# Arduino-Teensy-v43_PLUS_ESP-12E.net
KiCad netlist of a schematic drawn in EAGLE
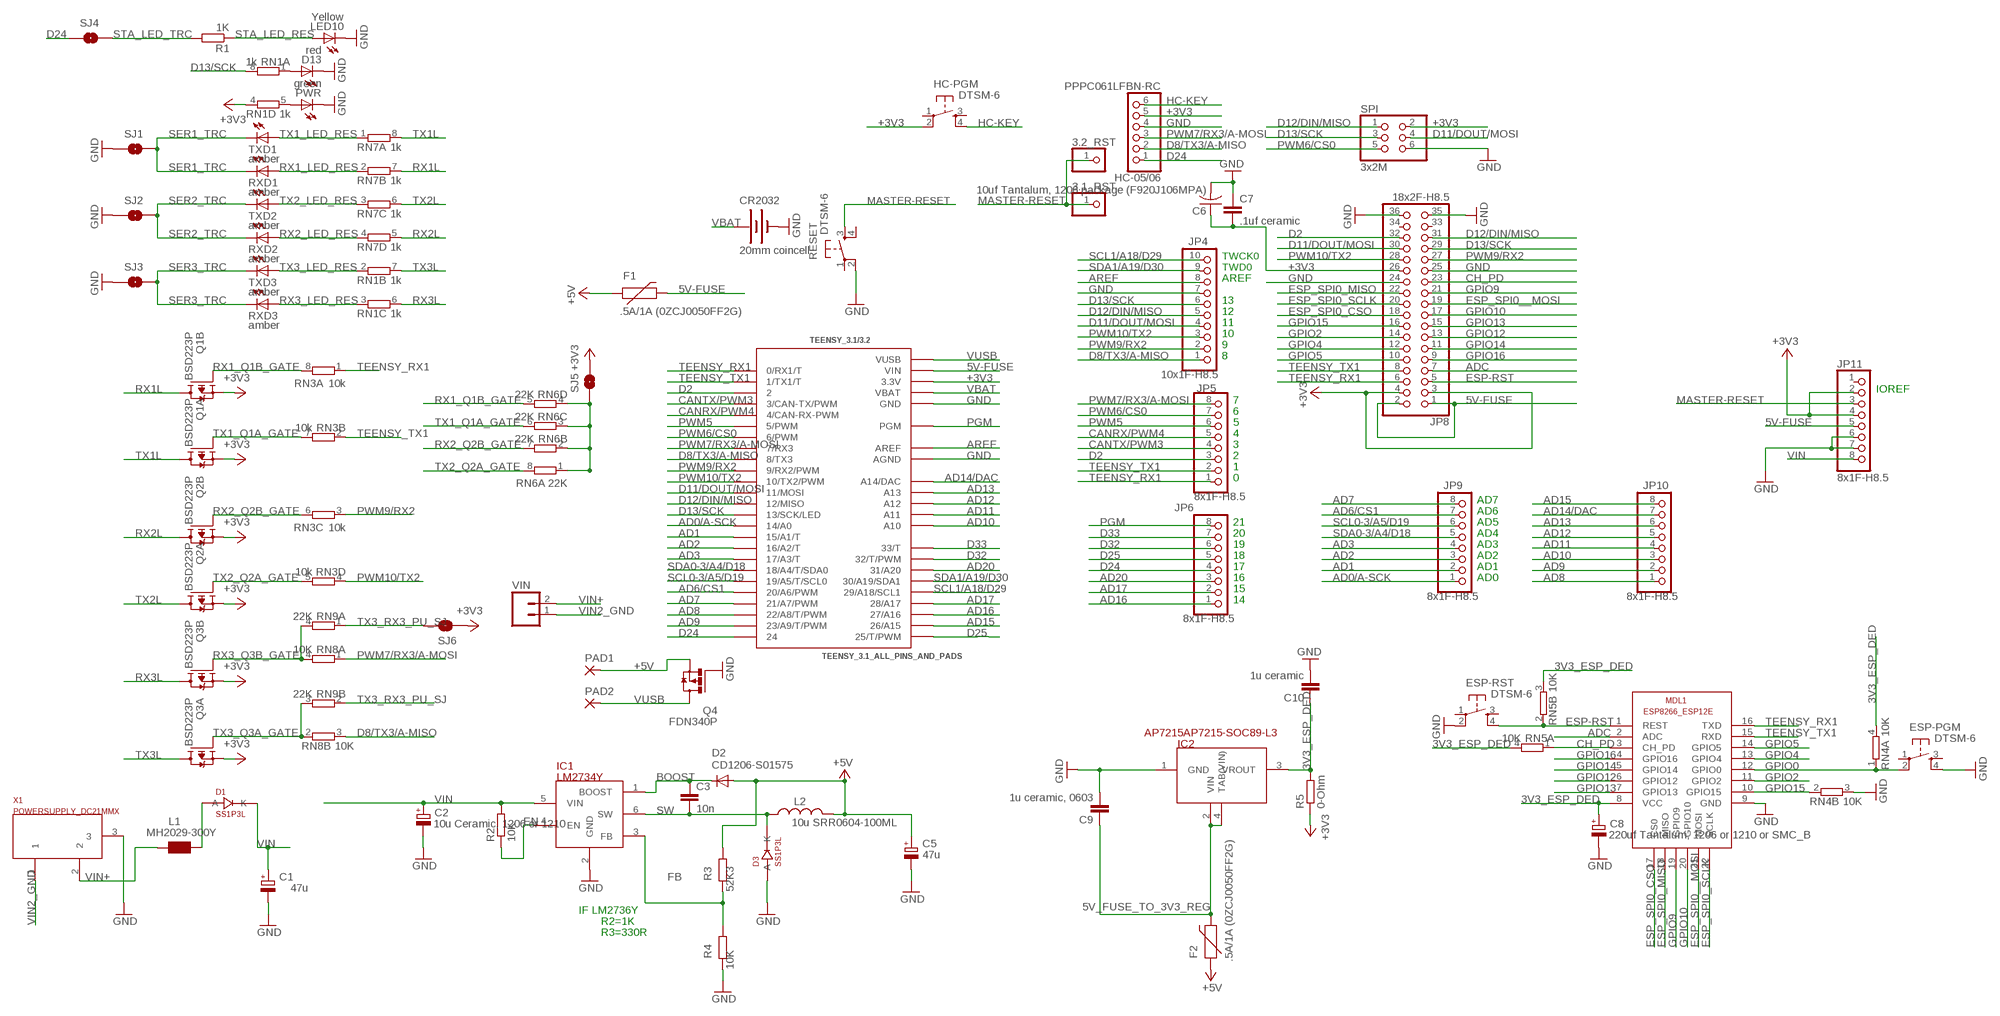
[diagram p0: schematic, sheet 1]

(export (version "E")
  (design (tool "Eeschema 10.0.6"))
  (components
    (comp (ref "3.1_RST")
      (value "PINHD-1X1CB")
      (footprint "eagle-import:1X01-CLEANBIG")
      (libsource (lib "eagle-import") (part "PINHD-1X1CB"))
    )
    (comp (ref "3.2_RST")
      (value "PINHD-1X1CB")
      (footprint "eagle-import:1X01-CLEANBIG")
      (libsource (lib "eagle-import") (part "PINHD-1X1CB"))
    )
    (comp (ref "C1")
      (value "47u")
      (footprint "eagle-import:PANASONIC_D")
      (libsource (lib "eagle-import") (part "CPOL-EUD"))
    )
    (comp (ref "C2")
      (value "10u Ceramic, 1206 or 1210")
      (footprint "eagle-import:SMC_B")
      (libsource (lib "eagle-import") (part "CPOL-EUSMCB"))
    )
    (comp (ref "C3")
      (value "10n")
      (footprint "eagle-import:C0603-ROUND")
      (libsource (lib "eagle-import") (part "C-EUC0603"))
    )
    (comp (ref "C5")
      (value "47u")
      (footprint "eagle-import:PANASONIC_D")
      (libsource (lib "eagle-import") (part "CPOL-EUD"))
    )
    (comp (ref "C6")
      (value "10uf Tantalum, 1206 package (F920J106MPA)")
      (footprint "eagle-import:C0805")
      (libsource (lib "eagle-import") (part "C-USC0805"))
    )
    (comp (ref "C7")
      (value ".1uf ceramic")
      (footprint "eagle-import:C0603-ROUND")
      (libsource (lib "eagle-import") (part "C-EUC0603"))
    )
    (comp (ref "C8")
      (value "220uf Tantalum, 1206 or 1210 or SMC_B")
      (footprint "eagle-import:SMC_B")
      (libsource (lib "eagle-import") (part "CPOL-EUSMCB"))
    )
    (comp (ref "C9")
      (value "1u ceramic, 0603")
      (footprint "eagle-import:C0603-ROUND")
      (libsource (lib "eagle-import") (part "C-EUC0603"))
    )
    (comp (ref "C10")
      (value "1u ceramic")
      (footprint "eagle-import:C0603-ROUND")
      (libsource (lib "eagle-import") (part "C-EUC0603"))
    )
    (comp (ref "CR2032")
      (value "20mm coincell")
      (footprint "eagle-import:BATTCON_20MM_4LEGS")
      (libsource (lib "eagle-import") (part "BATTERY20MM_4LEGS"))
    )
    (comp (ref "D1")
      (value "SS1P3L")
      (footprint "eagle-import:DO220AAL")
      (libsource (lib "eagle-import") (part "SS1P3L"))
    )
    (comp (ref "D2")
      (value "CD1206-S01575")
      (footprint "eagle-import:MINIMELF")
      (libsource (lib "eagle-import") (part "DIODE-MINIMELF"))
    )
    (comp (ref "D3")
      (value "SS1P3L")
      (footprint "eagle-import:DO220AAL")
      (libsource (lib "eagle-import") (part "SS1P3L"))
    )
    (comp (ref "D13")
      (value "red")
      (footprint "eagle-import:CHIPLED_0805")
      (libsource (lib "eagle-import") (part "LEDCHIPLED_0805"))
    )
    (comp (ref "ESP-PGM")
      (value "DTSM-6")
      (footprint "eagle-import:DTSM-6")
      (libsource (lib "eagle-import") (part "DTSM-6"))
    )
    (comp (ref "ESP-RST")
      (value "DTSM-6")
      (footprint "eagle-import:DTSM-6")
      (libsource (lib "eagle-import") (part "DTSM-6"))
    )
    (comp (ref "F1")
      (value ".5A/1A (0ZCJ0050FF2G)")
      (footprint "eagle-import:PTC-1206")
      (libsource (lib "eagle-import") (part "PTCSMD"))
    )
    (comp (ref "F2")
      (value ".5A/1A (0ZCJ0050FF2G)")
      (footprint "eagle-import:PTC-1206")
      (libsource (lib "eagle-import") (part "PTCSMD"))
    )
    (comp (ref "HC-05/06")
      (value "PPPC061LFBN-RC")
      (footprint "eagle-import:1X06")
      (libsource (lib "eagle-import") (part "PINHD-1X6"))
    )
    (comp (ref "HC-PGM")
      (value "DTSM-6")
      (footprint "eagle-import:DTSM-6")
      (libsource (lib "eagle-import") (part "DTSM-6"))
    )
    (comp (ref "IC1")
      (value "LM2734Y")
      (footprint "eagle-import:SOT23-6")
      (libsource (lib "eagle-import") (part "LM2736Y"))
    )
    (comp (ref "IC2")
      (value "AP7215AP7215-SOC89-L3")
      (footprint "eagle-import:SOC89-L3")
      (libsource (lib "eagle-import") (part "AP7215AP7215-SOC89-L3"))
    )
    (comp (ref "JP4")
      (value "10x1F-H8.5")
      (footprint "eagle-import:1X10")
      (libsource (lib "eagle-import") (part "PINHD-1X10"))
    )
    (comp (ref "JP5")
      (value "8x1F-H8.5")
      (footprint "eagle-import:1X08")
      (libsource (lib "eagle-import") (part "PINHD-1X8"))
    )
    (comp (ref "JP6")
      (value "8x1F-H8.5")
      (footprint "eagle-import:1X08")
      (libsource (lib "eagle-import") (part "PINHD-1X8"))
    )
    (comp (ref "JP8")
      (value "18x2F-H8.5")
      (footprint "eagle-import:2X18")
      (libsource (lib "eagle-import") (part "PINHD-2X18"))
    )
    (comp (ref "JP9")
      (value "8x1F-H8.5")
      (footprint "eagle-import:1X08")
      (libsource (lib "eagle-import") (part "PINHD-1X8"))
    )
    (comp (ref "JP10")
      (value "8x1F-H8.5")
      (footprint "eagle-import:1X08")
      (libsource (lib "eagle-import") (part "PINHD-1X8"))
    )
    (comp (ref "JP11")
      (value "8x1F-H8.5")
      (footprint "eagle-import:1X08")
      (libsource (lib "eagle-import") (part "PINHD-1X8"))
    )
    (comp (ref "L1")
      (value "MH2029-300Y")
      (footprint "eagle-import:0805")
      (libsource (lib "eagle-import") (part "WE-CBF_0805"))
    )
    (comp (ref "L2")
      (value "10u SRR0604-100ML")
      (footprint "eagle-import:SRR0604")
      (libsource (lib "eagle-import") (part "L-USSRR0604"))
    )
    (comp (ref "LED10")
      (value "Yellow")
      (footprint "eagle-import:CHIPLED_0805")
      (libsource (lib "eagle-import") (part "LEDCHIPLED_0805"))
    )
    (comp (ref "MDL1")
      (value "ESP8266-12E)")
      (footprint "eagle-import:ESP8266-ESP12E")
      (libsource (lib "eagle-import") (part "ESP8266-12EESP8266-ESP12E"))
    )
    (comp (ref "PAD1")
      (value "SMD2")
      (footprint "eagle-import:SMD1,27-2,54")
      (libsource (lib "eagle-import") (part "SMD2"))
    )
    (comp (ref "PAD2")
      (value "SMD2")
      (footprint "eagle-import:SMD1,27-2,54")
      (libsource (lib "eagle-import") (part "SMD2"))
    )
    (comp (ref "PWR")
      (value "green")
      (footprint "eagle-import:CHIPLED_0805")
      (libsource (lib "eagle-import") (part "LEDCHIPLED_0805"))
    )
    (comp (ref "Q1")
      (value "BSD223P")
      (footprint "eagle-import:SOT363_INFINEON")
      (libsource (lib "eagle-import") (part "BSD223P"))
    )
    (comp (ref "Q2")
      (value "BSD223P")
      (footprint "eagle-import:SOT363_INFINEON")
      (libsource (lib "eagle-import") (part "BSD223P"))
    )
    (comp (ref "Q3")
      (value "BSD223P")
      (footprint "eagle-import:SOT363_INFINEON")
      (libsource (lib "eagle-import") (part "BSD223P"))
    )
    (comp (ref "Q4")
      (value "FDN340P")
      (footprint "eagle-import:SUPER-SOT3")
      (libsource (lib "eagle-import") (part "FDN360P"))
    )
    (comp (ref "R1")
      (value "1K")
      (footprint "eagle-import:R0603")
      (libsource (lib "eagle-import") (part "rcl_R-EU_R0603"))
    )
    (comp (ref "R2")
      (value "10K")
      (footprint "eagle-import:R0603")
      (libsource (lib "eagle-import") (part "rcl_R-EU_R0603"))
    )
    (comp (ref "R3")
      (value "52K3")
      (footprint "eagle-import:R0603-ROUND")
      (libsource (lib "eagle-import") (part "R-EU_0603-RND"))
    )
    (comp (ref "R4")
      (value "10K")
      (footprint "eagle-import:R0603-ROUND")
      (libsource (lib "eagle-import") (part "R-EU_0603-RND"))
    )
    (comp (ref "R5")
      (value "0-Ohm")
      (footprint "eagle-import:R0603")
      (libsource (lib "eagle-import") (part "rcl_R-EU_R0603"))
    )
    (comp (ref "RESET")
      (value "DTSM-6")
      (footprint "eagle-import:DTSM-6")
      (libsource (lib "eagle-import") (part "DTSM-6"))
    )
    (comp (ref "RN1")
      (value "1k")
      (footprint "eagle-import:CAT16")
      (libsource (lib "eagle-import") (part "4R-NCAT16"))
    )
    (comp (ref "RN3")
      (value "10k")
      (footprint "eagle-import:CAT16")
      (libsource (lib "eagle-import") (part "4R-NCAT16"))
    )
    (comp (ref "RN4")
      (value "10K")
      (footprint "eagle-import:EXB34V")
      (libsource (lib "eagle-import") (part "2R-NEXB34V"))
    )
    (comp (ref "RN5")
      (value "10K")
      (footprint "eagle-import:EXB34V")
      (libsource (lib "eagle-import") (part "2R-NEXB34V"))
    )
    (comp (ref "RN6")
      (value "22K")
      (footprint "eagle-import:CAT16")
      (libsource (lib "eagle-import") (part "4R-NCAT16"))
    )
    (comp (ref "RN7")
      (value "1k")
      (footprint "eagle-import:CAT16")
      (libsource (lib "eagle-import") (part "4R-NCAT16"))
    )
    (comp (ref "RN8")
      (value "10K")
      (footprint "eagle-import:EXB34V")
      (libsource (lib "eagle-import") (part "2R-NEXB34V"))
    )
    (comp (ref "RN9")
      (value "22K")
      (footprint "eagle-import:EXB34V")
      (libsource (lib "eagle-import") (part "2R-NEXB34V"))
    )
    (comp (ref "RXD1")
      (value "amber")
      (footprint "eagle-import:CHIPLED_0805")
      (libsource (lib "eagle-import") (part "LEDCHIPLED_0805"))
    )
    (comp (ref "RXD2")
      (value "amber")
      (footprint "eagle-import:CHIPLED_0805")
      (libsource (lib "eagle-import") (part "LEDCHIPLED_0805"))
    )
    (comp (ref "RXD3")
      (value "amber")
      (footprint "eagle-import:CHIPLED_0805")
      (libsource (lib "eagle-import") (part "LEDCHIPLED_0805"))
    )
    (comp (ref "SJ1")
      (value "SOLDERJUMPERTRACE")
      (footprint "eagle-import:SJ_2S-TRACE")
      (libsource (lib "eagle-import") (part "SOLDERJUMPERTRACE"))
    )
    (comp (ref "SJ2")
      (value "SOLDERJUMPERTRACE")
      (footprint "eagle-import:SJ_2S-TRACE")
      (libsource (lib "eagle-import") (part "SOLDERJUMPERTRACE"))
    )
    (comp (ref "SJ3")
      (value "SOLDERJUMPERTRACE")
      (footprint "eagle-import:SJ_2S-TRACE")
      (libsource (lib "eagle-import") (part "SOLDERJUMPERTRACE"))
    )
    (comp (ref "SJ4")
      (value "SOLDERJUMPERTRACE")
      (footprint "eagle-import:SJ_2S-TRACE")
      (libsource (lib "eagle-import") (part "SOLDERJUMPERTRACE"))
    )
    (comp (ref "SJ5")
      (value "SOLDERJUMPERTRACE")
      (footprint "eagle-import:SJ_2S-TRACE")
      (libsource (lib "eagle-import") (part "SOLDERJUMPERTRACE"))
    )
    (comp (ref "SJ6")
      (value "SOLDERJUMPERTRACE")
      (footprint "eagle-import:SJ_2S-TRACE")
      (libsource (lib "eagle-import") (part "SOLDERJUMPERTRACE"))
    )
    (comp (ref "SPI")
      (value "3x2M")
      (footprint "eagle-import:2X03")
      (libsource (lib "eagle-import") (part "PINHD-2X3"))
    )
    (comp (ref "TEENSY_3.1/3.2")
      (value "TEENSY_3.1_ALL_PINS_AND_PADS")
      (footprint "eagle-import:TEENSY3_ALL_PINS_&_PADS")
      (libsource (lib "eagle-import") (part "TEENSY_3.1_ALL_PINS_AND_PADS"))
    )
    (comp (ref "TXD1")
      (value "amber")
      (footprint "eagle-import:CHIPLED_0805")
      (libsource (lib "eagle-import") (part "LEDCHIPLED_0805"))
    )
    (comp (ref "TXD2")
      (value "amber")
      (footprint "eagle-import:CHIPLED_0805")
      (libsource (lib "eagle-import") (part "LEDCHIPLED_0805"))
    )
    (comp (ref "TXD3")
      (value "amber")
      (footprint "eagle-import:CHIPLED_0805")
      (libsource (lib "eagle-import") (part "LEDCHIPLED_0805"))
    )
    (comp (ref "VIN")
      (value "M02LOCK_LONGPADS")
      (footprint "eagle-import:1X02_LOCK_LONGPADS")
      (libsource (lib "eagle-import") (part "M02LOCK_LONGPADS"))
    )
    (comp (ref "X1")
      (value "POWERSUPPLY_DC21MMX")
      (footprint "eagle-import:POWERSUPPLY_DC-21MM")
      (libsource (lib "eagle-import") (part "POWERSUPPLY_DC21MMX"))
    )
  )
  (nets
    (net (code "1") (name "+3V3") (class "Default")
      (node (ref "C6") (pin "1") (pinfunction "1_1") (pintype "passive"))
      (node (ref "C7") (pin "2") (pinfunction "2_2") (pintype "passive"))
      (node (ref "HC-05/06") (pin "5") (pinfunction "5_5") (pintype "passive"))
      (node (ref "HC-PGM") (pin "2") (pinfunction "2_2") (pintype "passive"))
      (node (ref "JP11") (pin "2") (pinfunction "2_2") (pintype "passive"))
      (node (ref "JP11") (pin "4") (pinfunction "4_4") (pintype "passive"))
      (node (ref "JP8") (pin "26") (pinfunction "26_26") (pintype "passive"))
      (node (ref "JP8") (pin "3") (pinfunction "3_3") (pintype "passive"))
      (node (ref "JP8") (pin "4") (pinfunction "4_4") (pintype "passive"))
      (node (ref "Q1") (pin "1") (pinfunction "S_1") (pintype "passive"))
      (node (ref "Q1") (pin "4") (pinfunction "S_4") (pintype "passive"))
      (node (ref "Q2") (pin "1") (pinfunction "S_1") (pintype "passive"))
      (node (ref "Q2") (pin "4") (pinfunction "S_4") (pintype "passive"))
      (node (ref "Q3") (pin "1") (pinfunction "S_1") (pintype "passive"))
      (node (ref "Q3") (pin "4") (pinfunction "S_4") (pintype "passive"))
      (node (ref "R5") (pin "1") (pinfunction "1_1") (pintype "passive"))
      (node (ref "RN1") (pin "4") (pinfunction "1_4") (pintype "passive"))
      (node (ref "SJ5") (pin "2") (pinfunction "2_2") (pintype "passive"))
      (node (ref "SJ6") (pin "1") (pinfunction "1_1") (pintype "passive"))
      (node (ref "SPI") (pin "2") (pinfunction "2_2") (pintype "passive"))
      (node (ref "TEENSY_3.1/3.2") (pin "3.3V") (pinfunction "3.3V_3.3V") (pintype "power_in"))
      (node (ref "TEENSY_3.1/3.2") (pin "3.3V1") (pinfunction "3.3V_3.3V1") (pintype "power_in"))
      (node (ref "TEENSY_3.1/3.2") (pin "3.3V2") (pinfunction "3.3V_3.3V2") (pintype "power_in"))
    )
    (net (code "2") (name "+5V") (class "Default")
      (node (ref "C5") (pin "+") (pinfunction "+_+") (pintype "passive"))
      (node (ref "D2") (pin "A") (pinfunction "A_A") (pintype "passive"))
      (node (ref "F1") (pin "1") (pinfunction "1_1") (pintype "bidirectional"))
      (node (ref "F2") (pin "1") (pinfunction "1_1") (pintype "bidirectional"))
      (node (ref "L2") (pin "P$2") (pinfunction "2_P$2") (pintype "passive"))
      (node (ref "PAD1") (pin "1") (pinfunction "P_1") (pintype "passive"))
      (node (ref "Q4") (pin "2") (pinfunction "S_2") (pintype "passive"))
      (node (ref "R3") (pin "1") (pinfunction "1_1") (pintype "passive"))
    )
    (net (code "3") (name "/3V3_ESP_DED") (class "Default")
      (node (ref "C10") (pin "1") (pinfunction "1_1") (pintype "passive"))
      (node (ref "C8") (pin "+") (pinfunction "+_+") (pintype "passive"))
      (node (ref "IC2") (pin "3") (pinfunction "VROUT_3") (pintype "output"))
      (node (ref "MDL1") (pin "8") (pinfunction "VCC_8") (pintype "bidirectional"))
      (node (ref "R5") (pin "2") (pinfunction "2_2") (pintype "passive"))
      (node (ref "RN4") (pin "4") (pinfunction "2_4") (pintype "passive"))
      (node (ref "RN5") (pin "3") (pinfunction "2_3") (pintype "passive"))
      (node (ref "RN5") (pin "4") (pinfunction "2_4") (pintype "passive"))
    )
    (net (code "4") (name "/5V-FUSE") (class "Default")
      (node (ref "F1") (pin "2") (pinfunction "2_2") (pintype "bidirectional"))
      (node (ref "JP11") (pin "5") (pinfunction "5_5") (pintype "passive"))
      (node (ref "JP8") (pin "1") (pinfunction "1_1") (pintype "passive"))
      (node (ref "JP8") (pin "2") (pinfunction "2_2") (pintype "passive"))
      (node (ref "TEENSY_3.1/3.2") (pin "VIN") (pinfunction "VIN_VIN") (pintype "power_in"))
    )
    (net (code "5") (name "/5V_FUSE_TO_3V3_REG") (class "Default")
      (node (ref "C9") (pin "1") (pinfunction "1_1") (pintype "passive"))
      (node (ref "F2") (pin "2") (pinfunction "2_2") (pintype "bidirectional"))
      (node (ref "IC2") (pin "2") (pinfunction "VIN_2") (pintype "input"))
      (node (ref "IC2") (pin "4") (pinfunction "TAB(VIN)_4") (pintype "input"))
    )
    (net (code "6") (name "/AD0{slash}A-SCK") (class "Default")
      (node (ref "JP9") (pin "1") (pinfunction "1_1") (pintype "passive"))
      (node (ref "TEENSY_3.1/3.2") (pin "14/A0") (pinfunction "14/A0_14/A0") (pintype "bidirectional"))
    )
    (net (code "7") (name "/AD1") (class "Default")
      (node (ref "JP9") (pin "2") (pinfunction "2_2") (pintype "passive"))
      (node (ref "TEENSY_3.1/3.2") (pin "15/A1") (pinfunction "15/A1/T_15/A1") (pintype "bidirectional"))
    )
    (net (code "8") (name "/AD2") (class "Default")
      (node (ref "JP9") (pin "3") (pinfunction "3_3") (pintype "passive"))
      (node (ref "TEENSY_3.1/3.2") (pin "16/A2") (pinfunction "16/A2/T_16/A2") (pintype "bidirectional"))
    )
    (net (code "9") (name "/AD3") (class "Default")
      (node (ref "JP9") (pin "4") (pinfunction "4_4") (pintype "passive"))
      (node (ref "TEENSY_3.1/3.2") (pin "17/A3") (pinfunction "17/A3/T_17/A3") (pintype "bidirectional"))
    )
    (net (code "10") (name "/AD6{slash}CS1") (class "Default")
      (node (ref "JP9") (pin "7") (pinfunction "7_7") (pintype "passive"))
      (node (ref "TEENSY_3.1/3.2") (pin "20/A6") (pinfunction "20/A6/PWM_20/A6") (pintype "bidirectional"))
    )
    (net (code "11") (name "/AD7") (class "Default")
      (node (ref "JP9") (pin "8") (pinfunction "8_8") (pintype "passive"))
      (node (ref "TEENSY_3.1/3.2") (pin "21/A7") (pinfunction "21/A7/PWM_21/A7") (pintype "bidirectional"))
    )
    (net (code "12") (name "/AD8") (class "Default")
      (node (ref "JP10") (pin "1") (pinfunction "1_1") (pintype "passive"))
      (node (ref "TEENSY_3.1/3.2") (pin "22/A8") (pinfunction "22/A8/T/PWM_22/A8") (pintype "bidirectional"))
    )
    (net (code "13") (name "/AD9") (class "Default")
      (node (ref "JP10") (pin "2") (pinfunction "2_2") (pintype "passive"))
      (node (ref "TEENSY_3.1/3.2") (pin "23/A9") (pinfunction "23/A9/T/PWM_23/A9") (pintype "bidirectional"))
    )
    (net (code "14") (name "/AD10") (class "Default")
      (node (ref "JP10") (pin "3") (pinfunction "3_3") (pintype "passive"))
      (node (ref "TEENSY_3.1/3.2") (pin "A10") (pinfunction "A10_A10") (pintype "bidirectional"))
    )
    (net (code "15") (name "/AD11") (class "Default")
      (node (ref "JP10") (pin "4") (pinfunction "4_4") (pintype "passive"))
      (node (ref "TEENSY_3.1/3.2") (pin "A11") (pinfunction "A11_A11") (pintype "bidirectional"))
    )
    (net (code "16") (name "/AD12") (class "Default")
      (node (ref "JP10") (pin "5") (pinfunction "5_5") (pintype "passive"))
      (node (ref "TEENSY_3.1/3.2") (pin "A12") (pinfunction "A12_A12") (pintype "bidirectional"))
    )
    (net (code "17") (name "/AD13") (class "Default")
      (node (ref "JP10") (pin "6") (pinfunction "6_6") (pintype "passive"))
      (node (ref "TEENSY_3.1/3.2") (pin "A13") (pinfunction "A13_A13") (pintype "bidirectional"))
    )
    (net (code "18") (name "/AD14{slash}DAC") (class "Default")
      (node (ref "JP10") (pin "7") (pinfunction "7_7") (pintype "passive"))
      (node (ref "TEENSY_3.1/3.2") (pin "RESET/DAC") (pinfunction "A14/DAC_RESET/DAC") (pintype "bidirectional"))
    )
    (net (code "19") (name "/AD15") (class "Default")
      (node (ref "JP10") (pin "8") (pinfunction "8_8") (pintype "passive"))
      (node (ref "TEENSY_3.1/3.2") (pin "26") (pinfunction "26/A15_26") (pintype "bidirectional"))
    )
    (net (code "20") (name "/AD16") (class "Default")
      (node (ref "JP6") (pin "1") (pinfunction "1_1") (pintype "passive"))
      (node (ref "TEENSY_3.1/3.2") (pin "27") (pinfunction "27/A16_27") (pintype "bidirectional"))
    )
    (net (code "21") (name "/AD17") (class "Default")
      (node (ref "JP6") (pin "2") (pinfunction "2_2") (pintype "passive"))
      (node (ref "TEENSY_3.1/3.2") (pin "28") (pinfunction "28/A17_28") (pintype "bidirectional"))
    )
    (net (code "22") (name "/AD20") (class "Default")
      (node (ref "JP6") (pin "3") (pinfunction "3_3") (pintype "passive"))
      (node (ref "TEENSY_3.1/3.2") (pin "31") (pinfunction "31/A20_31") (pintype "bidirectional"))
    )
    (net (code "23") (name "/ADC") (class "Default")
      (node (ref "JP8") (pin "7") (pinfunction "7_7") (pintype "passive"))
      (node (ref "MDL1") (pin "2") (pinfunction "ADC_2") (pintype "bidirectional"))
    )
    (net (code "24") (name "/AREF") (class "Default")
      (node (ref "JP4") (pin "8") (pinfunction "8_8") (pintype "passive"))
      (node (ref "TEENSY_3.1/3.2") (pin "AREF") (pinfunction "AREF_AREF") (pintype "power_in"))
    )
    (net (code "25") (name "/BOOST") (class "Default")
      (node (ref "C3") (pin "1") (pinfunction "1_1") (pintype "passive"))
      (node (ref "D2") (pin "C") (pinfunction "C_C") (pintype "passive"))
      (node (ref "IC1") (pin "1") (pinfunction "BOOST_1") (pintype "input"))
    )
    (net (code "26") (name "/CANRX{slash}PWM4") (class "Default")
      (node (ref "JP5") (pin "5") (pinfunction "5_5") (pintype "passive"))
      (node (ref "TEENSY_3.1/3.2") (pin "4") (pinfunction "4/CAN-RX-PWM_4") (pintype "bidirectional"))
    )
    (net (code "27") (name "/CANTX{slash}PWM3") (class "Default")
      (node (ref "JP5") (pin "4") (pinfunction "4_4") (pintype "passive"))
      (node (ref "TEENSY_3.1/3.2") (pin "3") (pinfunction "3/CAN-TX/PWM_3") (pintype "bidirectional"))
    )
    (net (code "28") (name "/CH_PD") (class "Default")
      (node (ref "JP8") (pin "23") (pinfunction "23_23") (pintype "passive"))
      (node (ref "MDL1") (pin "3") (pinfunction "CH_PD_3") (pintype "bidirectional"))
      (node (ref "RN5") (pin "1") (pinfunction "1_1") (pintype "passive"))
    )
    (net (code "29") (name "/D2") (class "Default")
      (node (ref "JP5") (pin "3") (pinfunction "3_3") (pintype "passive"))
      (node (ref "JP8") (pin "32") (pinfunction "32_32") (pintype "passive"))
      (node (ref "TEENSY_3.1/3.2") (pin "2") (pinfunction "2_2") (pintype "bidirectional"))
    )
    (net (code "30") (name "/D8{slash}TX3{slash}A-MISO") (class "Default")
      (node (ref "HC-05/06") (pin "2") (pinfunction "2_2") (pintype "passive"))
      (node (ref "JP4") (pin "1") (pinfunction "1_1") (pintype "passive"))
      (node (ref "RN8") (pin "3") (pinfunction "2_3") (pintype "passive"))
      (node (ref "TEENSY_3.1/3.2") (pin "8") (pinfunction "8/TX3_8") (pintype "bidirectional"))
    )
    (net (code "31") (name "/D11{slash}DOUT{slash}MOSI") (class "Default")
      (node (ref "JP4") (pin "4") (pinfunction "4_4") (pintype "passive"))
      (node (ref "JP8") (pin "30") (pinfunction "30_30") (pintype "passive"))
      (node (ref "SPI") (pin "4") (pinfunction "4_4") (pintype "passive"))
      (node (ref "TEENSY_3.1/3.2") (pin "11") (pinfunction "11/MOSI_11") (pintype "bidirectional"))
    )
    (net (code "32") (name "/D12{slash}DIN{slash}MISO") (class "Default")
      (node (ref "JP4") (pin "5") (pinfunction "5_5") (pintype "passive"))
      (node (ref "JP8") (pin "31") (pinfunction "31_31") (pintype "passive"))
      (node (ref "SPI") (pin "1") (pinfunction "1_1") (pintype "passive"))
      (node (ref "TEENSY_3.1/3.2") (pin "12") (pinfunction "12/MISO_12") (pintype "bidirectional"))
    )
    (net (code "33") (name "/D13{slash}SCK") (class "Default")
      (node (ref "JP4") (pin "6") (pinfunction "6_6") (pintype "passive"))
      (node (ref "JP8") (pin "29") (pinfunction "29_29") (pintype "passive"))
      (node (ref "RN1") (pin "8") (pinfunction "2_8") (pintype "passive"))
      (node (ref "SPI") (pin "3") (pinfunction "3_3") (pintype "passive"))
      (node (ref "TEENSY_3.1/3.2") (pin "13") (pinfunction "13/SCK/LED_13") (pintype "bidirectional"))
    )
    (net (code "34") (name "/D24") (class "Default")
      (node (ref "HC-05/06") (pin "1") (pinfunction "1_1") (pintype "passive"))
      (node (ref "JP6") (pin "4") (pinfunction "4_4") (pintype "passive"))
      (node (ref "SJ4") (pin "1") (pinfunction "1_1") (pintype "passive"))
      (node (ref "TEENSY_3.1/3.2") (pin "24") (pinfunction "24_24") (pintype "bidirectional"))
    )
    (net (code "35") (name "/D25") (class "Default")
      (node (ref "JP6") (pin "5") (pinfunction "5_5") (pintype "passive"))
      (node (ref "TEENSY_3.1/3.2") (pin "25") (pinfunction "25/T/PWM_25") (pintype "bidirectional"))
    )
    (net (code "36") (name "/D32") (class "Default")
      (node (ref "JP6") (pin "6") (pinfunction "6_6") (pintype "passive"))
      (node (ref "TEENSY_3.1/3.2") (pin "32") (pinfunction "32/T/PWM_32") (pintype "bidirectional"))
    )
    (net (code "37") (name "/D33") (class "Default")
      (node (ref "JP6") (pin "7") (pinfunction "7_7") (pintype "passive"))
      (node (ref "TEENSY_3.1/3.2") (pin "33") (pinfunction "33/T_33") (pintype "bidirectional"))
    )
    (net (code "38") (name "/EN") (class "Default")
      (node (ref "IC1") (pin "4") (pinfunction "EN_4") (pintype "input"))
      (node (ref "R2") (pin "1") (pinfunction "1_1") (pintype "passive"))
    )
    (net (code "39") (name "/ESP-RST") (class "Default")
      (node (ref "ESP-RST") (pin "4") (pinfunction "4_4") (pintype "passive"))
      (node (ref "JP8") (pin "5") (pinfunction "5_5") (pintype "passive"))
      (node (ref "MDL1") (pin "1") (pinfunction "REST_1") (pintype "bidirectional"))
      (node (ref "RN5") (pin "2") (pinfunction "1_2") (pintype "passive"))
    )
    (net (code "40") (name "/ESP_SPI0_CSO") (class "Default")
      (node (ref "JP8") (pin "18") (pinfunction "18_18") (pintype "passive"))
      (node (ref "MDL1") (pin "17") (pinfunction "CS0_17") (pintype "bidirectional"))
    )
    (net (code "41") (name "/ESP_SPI0_MISO") (class "Default")
      (node (ref "JP8") (pin "22") (pinfunction "22_22") (pintype "passive"))
      (node (ref "MDL1") (pin "18") (pinfunction "MISO_18") (pintype "bidirectional"))
    )
    (net (code "42") (name "/ESP_SPI0_SCLK") (class "Default")
      (node (ref "JP8") (pin "20") (pinfunction "20_20") (pintype "passive"))
      (node (ref "MDL1") (pin "22") (pinfunction "SCLK_22") (pintype "bidirectional"))
    )
    (net (code "43") (name "/ESP_SPI0__MOSI") (class "Default")
      (node (ref "JP8") (pin "19") (pinfunction "19_19") (pintype "passive"))
      (node (ref "MDL1") (pin "21") (pinfunction "MOSI_21") (pintype "bidirectional"))
    )
    (net (code "44") (name "/FB") (class "Default")
      (node (ref "IC1") (pin "3") (pinfunction "FB_3") (pintype "input"))
      (node (ref "R3") (pin "2") (pinfunction "2_2") (pintype "passive"))
      (node (ref "R4") (pin "1") (pinfunction "1_1") (pintype "passive"))
    )
    (net (code "45") (name "/GPIO0") (class "Default")
      (node (ref "ESP-PGM") (pin "2") (pinfunction "2_2") (pintype "passive"))
      (node (ref "MDL1") (pin "12") (pinfunction "GPIO0_12") (pintype "bidirectional"))
      (node (ref "RN4") (pin "1") (pinfunction "1_1") (pintype "passive"))
    )
    (net (code "46") (name "/GPIO2") (class "Default")
      (node (ref "JP8") (pin "14") (pinfunction "14_14") (pintype "passive"))
      (node (ref "MDL1") (pin "11") (pinfunction "GPIO2_11") (pintype "bidirectional"))
    )
    (net (code "47") (name "/GPIO4") (class "Default")
      (node (ref "JP8") (pin "12") (pinfunction "12_12") (pintype "passive"))
      (node (ref "MDL1") (pin "13") (pinfunction "GPIO4_13") (pintype "bidirectional"))
    )
    (net (code "48") (name "/GPIO5") (class "Default")
      (node (ref "JP8") (pin "10") (pinfunction "10_10") (pintype "passive"))
      (node (ref "MDL1") (pin "14") (pinfunction "GPIO5_14") (pintype "bidirectional"))
    )
    (net (code "49") (name "/GPIO9") (class "Default")
      (node (ref "JP8") (pin "21") (pinfunction "21_21") (pintype "passive"))
      (node (ref "MDL1") (pin "19") (pinfunction "GPIO9_19") (pintype "bidirectional"))
    )
    (net (code "50") (name "/GPIO10") (class "Default")
      (node (ref "JP8") (pin "17") (pinfunction "17_17") (pintype "passive"))
      (node (ref "MDL1") (pin "20") (pinfunction "GPIO10_20") (pintype "bidirectional"))
    )
    (net (code "51") (name "/GPIO12") (class "Default")
      (node (ref "JP8") (pin "13") (pinfunction "13_13") (pintype "passive"))
      (node (ref "MDL1") (pin "6") (pinfunction "GPIO12_6") (pintype "bidirectional"))
    )
    (net (code "52") (name "/GPIO13") (class "Default")
      (node (ref "JP8") (pin "15") (pinfunction "15_15") (pintype "passive"))
      (node (ref "MDL1") (pin "7") (pinfunction "GPIO13_7") (pintype "bidirectional"))
    )
    (net (code "53") (name "/GPIO14") (class "Default")
      (node (ref "JP8") (pin "11") (pinfunction "11_11") (pintype "passive"))
      (node (ref "MDL1") (pin "5") (pinfunction "GPIO14_5") (pintype "bidirectional"))
    )
    (net (code "54") (name "/GPIO15") (class "Default")
      (node (ref "JP8") (pin "16") (pinfunction "16_16") (pintype "passive"))
      (node (ref "MDL1") (pin "10") (pinfunction "GPIO15_10") (pintype "bidirectional"))
      (node (ref "RN4") (pin "2") (pinfunction "1_2") (pintype "passive"))
    )
    (net (code "55") (name "/GPIO16") (class "Default")
      (node (ref "JP8") (pin "9") (pinfunction "9_9") (pintype "passive"))
      (node (ref "MDL1") (pin "4") (pinfunction "GPIO16_4") (pintype "bidirectional"))
    )
    (net (code "56") (name "/HC-KEY") (class "Default")
      (node (ref "HC-05/06") (pin "6") (pinfunction "6_6") (pintype "passive"))
      (node (ref "HC-PGM") (pin "4") (pinfunction "4_4") (pintype "passive"))
    )
    (net (code "57") (name "/MASTER-RESET") (class "Default")
      (node (ref "3.1_RST") (pin "1") (pinfunction "1_1") (pintype "passive"))
      (node (ref "3.2_RST") (pin "1") (pinfunction "1_1") (pintype "passive"))
      (node (ref "JP11") (pin "3") (pinfunction "3_3") (pintype "passive"))
      (node (ref "RESET") (pin "3") (pinfunction "3_3") (pintype "passive"))
    )
    (net (code "58") (name "/PGM") (class "Default")
      (node (ref "JP6") (pin "8") (pinfunction "8_8") (pintype "passive"))
      (node (ref "TEENSY_3.1/3.2") (pin "PGM") (pinfunction "PGM_PGM") (pintype "bidirectional"))
    )
    (net (code "59") (name "/PWM5") (class "Default")
      (node (ref "JP5") (pin "6") (pinfunction "6_6") (pintype "passive"))
      (node (ref "TEENSY_3.1/3.2") (pin "5") (pinfunction "5/PWM_5") (pintype "bidirectional"))
    )
    (net (code "60") (name "/PWM6{slash}CS0") (class "Default")
      (node (ref "JP5") (pin "7") (pinfunction "7_7") (pintype "passive"))
      (node (ref "SPI") (pin "5") (pinfunction "5_5") (pintype "passive"))
      (node (ref "TEENSY_3.1/3.2") (pin "6") (pinfunction "6/PWM_6") (pintype "bidirectional"))
    )
    (net (code "61") (name "/PWM7{slash}RX3{slash}A-MOSI") (class "Default")
      (node (ref "HC-05/06") (pin "3") (pinfunction "3_3") (pintype "passive"))
      (node (ref "JP5") (pin "8") (pinfunction "8_8") (pintype "passive"))
      (node (ref "RN8") (pin "1") (pinfunction "1_1") (pintype "passive"))
      (node (ref "TEENSY_3.1/3.2") (pin "7") (pinfunction "7/RX3_7") (pintype "bidirectional"))
    )
    (net (code "62") (name "/PWM9{slash}RX2") (class "Default")
      (node (ref "JP4") (pin "2") (pinfunction "2_2") (pintype "passive"))
      (node (ref "JP8") (pin "27") (pinfunction "27_27") (pintype "passive"))
      (node (ref "RN3") (pin "3") (pinfunction "1_3") (pintype "passive"))
      (node (ref "TEENSY_3.1/3.2") (pin "9") (pinfunction "9/RX2/PWM_9") (pintype "bidirectional"))
    )
    (net (code "63") (name "/PWM10{slash}TX2") (class "Default")
      (node (ref "JP4") (pin "3") (pinfunction "3_3") (pintype "passive"))
      (node (ref "JP8") (pin "28") (pinfunction "28_28") (pintype "passive"))
      (node (ref "RN3") (pin "4") (pinfunction "1_4") (pintype "passive"))
      (node (ref "TEENSY_3.1/3.2") (pin "10") (pinfunction "10/TX2/PWM_10") (pintype "bidirectional"))
    )
    (net (code "64") (name "/RX1L") (class "Default")
      (node (ref "Q1") (pin "3") (pinfunction "D_3") (pintype "passive"))
      (node (ref "RN7") (pin "7") (pinfunction "2_7") (pintype "passive"))
    )
    (net (code "65") (name "/RX1_LED_RES") (class "Default")
      (node (ref "RN7") (pin "2") (pinfunction "1_2") (pintype "passive"))
      (node (ref "RXD1") (pin "A") (pinfunction "A_A") (pintype "passive"))
    )
    (net (code "66") (name "/RX1_Q1B_GATE") (class "Default")
      (node (ref "Q1") (pin "5") (pinfunction "G_5") (pintype "passive"))
      (node (ref "RN3") (pin "8") (pinfunction "2_8") (pintype "passive"))
      (node (ref "RN6") (pin "5") (pinfunction "2_5") (pintype "passive"))
    )
    (net (code "67") (name "/RX2L") (class "Default")
      (node (ref "Q2") (pin "3") (pinfunction "D_3") (pintype "passive"))
      (node (ref "RN7") (pin "5") (pinfunction "2_5") (pintype "passive"))
    )
    (net (code "68") (name "/RX2_LED_RES") (class "Default")
      (node (ref "RN7") (pin "4") (pinfunction "1_4") (pintype "passive"))
      (node (ref "RXD2") (pin "A") (pinfunction "A_A") (pintype "passive"))
    )
    (net (code "69") (name "/RX2_Q2B_GATE") (class "Default")
      (node (ref "Q2") (pin "5") (pinfunction "G_5") (pintype "passive"))
      (node (ref "RN3") (pin "6") (pinfunction "2_6") (pintype "passive"))
      (node (ref "RN6") (pin "7") (pinfunction "2_7") (pintype "passive"))
    )
    (net (code "70") (name "/RX3L") (class "Default")
      (node (ref "Q3") (pin "3") (pinfunction "D_3") (pintype "passive"))
      (node (ref "RN1") (pin "6") (pinfunction "2_6") (pintype "passive"))
    )
    (net (code "71") (name "/RX3_LED_RES") (class "Default")
      (node (ref "RN1") (pin "3") (pinfunction "1_3") (pintype "passive"))
      (node (ref "RXD3") (pin "A") (pinfunction "A_A") (pintype "passive"))
    )
    (net (code "72") (name "/RX3_Q3B_GATE") (class "Default")
      (node (ref "Q3") (pin "5") (pinfunction "G_5") (pintype "passive"))
      (node (ref "RN8") (pin "4") (pinfunction "2_4") (pintype "passive"))
      (node (ref "RN9") (pin "4") (pinfunction "2_4") (pintype "passive"))
    )
    (net (code "73") (name "/SCL0-3{slash}A5{slash}D19") (class "Default")
      (node (ref "JP9") (pin "6") (pinfunction "6_6") (pintype "passive"))
      (node (ref "TEENSY_3.1/3.2") (pin "19/A5") (pinfunction "19/A5/T/SCL0_19/A5") (pintype "bidirectional"))
    )
    (net (code "74") (name "/SCL1{slash}A18{slash}D29") (class "Default")
      (node (ref "JP4") (pin "10") (pinfunction "10_10") (pintype "passive"))
      (node (ref "TEENSY_3.1/3.2") (pin "29") (pinfunction "29/A18/SCL1_29") (pintype "bidirectional"))
    )
    (net (code "75") (name "/SDA0-3{slash}A4{slash}D18") (class "Default")
      (node (ref "JP9") (pin "5") (pinfunction "5_5") (pintype "passive"))
      (node (ref "TEENSY_3.1/3.2") (pin "18/A4") (pinfunction "18/A4/T/SDA0_18/A4") (pintype "bidirectional"))
    )
    (net (code "76") (name "/SDA1{slash}A19{slash}D30") (class "Default")
      (node (ref "JP4") (pin "9") (pinfunction "9_9") (pintype "passive"))
      (node (ref "TEENSY_3.1/3.2") (pin "30") (pinfunction "30/A19/SDA1_30") (pintype "bidirectional"))
    )
    (net (code "77") (name "/SER1_TRC") (class "Default")
      (node (ref "RXD1") (pin "C") (pinfunction "C_C") (pintype "passive"))
      (node (ref "SJ1") (pin "2") (pinfunction "2_2") (pintype "passive"))
      (node (ref "TXD1") (pin "C") (pinfunction "C_C") (pintype "passive"))
    )
    (net (code "78") (name "/SER2_TRC") (class "Default")
      (node (ref "RXD2") (pin "C") (pinfunction "C_C") (pintype "passive"))
      (node (ref "SJ2") (pin "2") (pinfunction "2_2") (pintype "passive"))
      (node (ref "TXD2") (pin "C") (pinfunction "C_C") (pintype "passive"))
    )
    (net (code "79") (name "/SER3_TRC") (class "Default")
      (node (ref "RXD3") (pin "C") (pinfunction "C_C") (pintype "passive"))
      (node (ref "SJ3") (pin "2") (pinfunction "2_2") (pintype "passive"))
      (node (ref "TXD3") (pin "C") (pinfunction "C_C") (pintype "passive"))
    )
    (net (code "80") (name "/STA_LED_RES") (class "Default")
      (node (ref "LED10") (pin "A") (pinfunction "A_A") (pintype "passive"))
      (node (ref "R1") (pin "1") (pinfunction "1_1") (pintype "passive"))
    )
    (net (code "81") (name "/STA_LED_TRC") (class "Default")
      (node (ref "R1") (pin "2") (pinfunction "2_2") (pintype "passive"))
      (node (ref "SJ4") (pin "2") (pinfunction "2_2") (pintype "passive"))
    )
    (net (code "82") (name "/SW") (class "Default")
      (node (ref "C3") (pin "2") (pinfunction "2_2") (pintype "passive"))
      (node (ref "D3") (pin "P$1") (pinfunction "K_P$1") (pintype "bidirectional"))
      (node (ref "IC1") (pin "6") (pinfunction "SW_6") (pintype "output"))
      (node (ref "L2") (pin "P$1") (pinfunction "1_P$1") (pintype "passive"))
    )
    (net (code "83") (name "/TEENSY_RX1") (class "Default")
      (node (ref "JP5") (pin "1") (pinfunction "1_1") (pintype "passive"))
      (node (ref "JP8") (pin "6") (pinfunction "6_6") (pintype "passive"))
      (node (ref "MDL1") (pin "16") (pinfunction "TXD_16") (pintype "bidirectional"))
      (node (ref "RN3") (pin "1") (pinfunction "1_1") (pintype "passive"))
      (node (ref "TEENSY_3.1/3.2") (pin "0") (pinfunction "0/RX1/T_0") (pintype "bidirectional"))
    )
    (net (code "84") (name "/TEENSY_TX1") (class "Default")
      (node (ref "JP5") (pin "2") (pinfunction "2_2") (pintype "passive"))
      (node (ref "JP8") (pin "8") (pinfunction "8_8") (pintype "passive"))
      (node (ref "MDL1") (pin "15") (pinfunction "RXD_15") (pintype "bidirectional"))
      (node (ref "RN3") (pin "2") (pinfunction "1_2") (pintype "passive"))
      (node (ref "TEENSY_3.1/3.2") (pin "1") (pinfunction "1/TX1/T_1") (pintype "bidirectional"))
    )
    (net (code "85") (name "/TX1L") (class "Default")
      (node (ref "Q1") (pin "6") (pinfunction "D_6") (pintype "passive"))
      (node (ref "RN7") (pin "8") (pinfunction "2_8") (pintype "passive"))
    )
    (net (code "86") (name "/TX1_LED_RES") (class "Default")
      (node (ref "RN7") (pin "1") (pinfunction "1_1") (pintype "passive"))
      (node (ref "TXD1") (pin "A") (pinfunction "A_A") (pintype "passive"))
    )
    (net (code "87") (name "/TX1_Q1A_GATE") (class "Default")
      (node (ref "Q1") (pin "2") (pinfunction "G_2") (pintype "passive"))
      (node (ref "RN3") (pin "7") (pinfunction "2_7") (pintype "passive"))
      (node (ref "RN6") (pin "6") (pinfunction "2_6") (pintype "passive"))
    )
    (net (code "88") (name "/TX2L") (class "Default")
      (node (ref "Q2") (pin "6") (pinfunction "D_6") (pintype "passive"))
      (node (ref "RN7") (pin "6") (pinfunction "2_6") (pintype "passive"))
    )
    (net (code "89") (name "/TX2_LED_RES") (class "Default")
      (node (ref "RN7") (pin "3") (pinfunction "1_3") (pintype "passive"))
      (node (ref "TXD2") (pin "A") (pinfunction "A_A") (pintype "passive"))
    )
    (net (code "90") (name "/TX2_Q2A_GATE") (class "Default")
      (node (ref "Q2") (pin "2") (pinfunction "G_2") (pintype "passive"))
      (node (ref "RN3") (pin "5") (pinfunction "2_5") (pintype "passive"))
      (node (ref "RN6") (pin "8") (pinfunction "2_8") (pintype "passive"))
    )
    (net (code "91") (name "/TX3L") (class "Default")
      (node (ref "Q3") (pin "6") (pinfunction "D_6") (pintype "passive"))
      (node (ref "RN1") (pin "7") (pinfunction "2_7") (pintype "passive"))
    )
    (net (code "92") (name "/TX3_LED_RES") (class "Default")
      (node (ref "RN1") (pin "2") (pinfunction "1_2") (pintype "passive"))
      (node (ref "TXD3") (pin "A") (pinfunction "A_A") (pintype "passive"))
    )
    (net (code "93") (name "/TX3_Q3A_GATE") (class "Default")
      (node (ref "Q3") (pin "2") (pinfunction "G_2") (pintype "passive"))
      (node (ref "RN8") (pin "2") (pinfunction "1_2") (pintype "passive"))
      (node (ref "RN9") (pin "3") (pinfunction "2_3") (pintype "passive"))
    )
    (net (code "94") (name "/TX3_RX3_PU_SJ") (class "Default")
      (node (ref "RN9") (pin "1") (pinfunction "1_1") (pintype "passive"))
      (node (ref "RN9") (pin "2") (pinfunction "1_2") (pintype "passive"))
      (node (ref "SJ6") (pin "2") (pinfunction "2_2") (pintype "passive"))
    )
    (net (code "95") (name "/VBAT") (class "Default")
      (node (ref "CR2032") (pin "POSITIVE@1") (pinfunction "+_POSITIVE@1") (pintype "power_in"))
      (node (ref "CR2032") (pin "POSITIVE@2") (pinfunction "+_POSITIVE@2") (pintype "power_in"))
      (node (ref "CR2032") (pin "POSITIVE@3") (pinfunction "+_POSITIVE@3") (pintype "power_in"))
      (node (ref "CR2032") (pin "POSITIVE@4") (pinfunction "+_POSITIVE@4") (pintype "power_in"))
      (node (ref "TEENSY_3.1/3.2") (pin "VBAT") (pinfunction "VBAT_VBAT") (pintype "power_in"))
    )
    (net (code "96") (name "/VIN") (class "Default")
      (node (ref "C1") (pin "+") (pinfunction "+_+") (pintype "passive"))
      (node (ref "C2") (pin "+") (pinfunction "+_+") (pintype "passive"))
      (node (ref "D1") (pin "P$1") (pinfunction "K_P$1") (pintype "bidirectional"))
      (node (ref "IC1") (pin "5") (pinfunction "VIN_5") (pintype "input"))
      (node (ref "JP11") (pin "8") (pinfunction "8_8") (pintype "passive"))
      (node (ref "R2") (pin "2") (pinfunction "2_2") (pintype "passive"))
    )
    (net (code "97") (name "/VIN+") (class "Default")
      (node (ref "L1") (pin "2") (pinfunction "2_2") (pintype "passive"))
      (node (ref "VIN") (pin "2") (pinfunction "2_2") (pintype "passive"))
      (node (ref "X1") (pin "2") (pinfunction "2_2") (pintype "power_in"))
    )
    (net (code "98") (name "/VIN2_GND") (class "Default")
      (node (ref "VIN") (pin "1") (pinfunction "1_1") (pintype "passive"))
      (node (ref "X1") (pin "1") (pinfunction "1_1") (pintype "power_in"))
    )
    (net (code "99") (name "/VUSB") (class "Default")
      (node (ref "PAD2") (pin "1") (pinfunction "P_1") (pintype "passive"))
      (node (ref "Q4") (pin "3") (pinfunction "D_3") (pintype "passive"))
      (node (ref "TEENSY_3.1/3.2") (pin "VUSB") (pinfunction "VUSB_VUSB") (pintype "power_in"))
    )
    (net (code "100") (name "GND") (class "Default")
      (node (ref "C1") (pin "-") (pinfunction "-_-") (pintype "passive"))
      (node (ref "C10") (pin "2") (pinfunction "2_2") (pintype "passive"))
      (node (ref "C2") (pin "-") (pinfunction "-_-") (pintype "passive"))
      (node (ref "C5") (pin "-") (pinfunction "-_-") (pintype "passive"))
      (node (ref "C6") (pin "2") (pinfunction "2_2") (pintype "passive"))
      (node (ref "C7") (pin "1") (pinfunction "1_1") (pintype "passive"))
      (node (ref "C8") (pin "-") (pinfunction "-_-") (pintype "passive"))
      (node (ref "C9") (pin "2") (pinfunction "2_2") (pintype "passive"))
      (node (ref "CR2032") (pin "NEGATIVE") (pinfunction "-_NEGATIVE") (pintype "power_in"))
      (node (ref "D13") (pin "C") (pinfunction "C_C") (pintype "passive"))
      (node (ref "D3") (pin "P$2") (pinfunction "A_P$2") (pintype "bidirectional"))
      (node (ref "ESP-PGM") (pin "4") (pinfunction "4_4") (pintype "passive"))
      (node (ref "ESP-RST") (pin "2") (pinfunction "2_2") (pintype "passive"))
      (node (ref "HC-05/06") (pin "4") (pinfunction "4_4") (pintype "passive"))
      (node (ref "IC1") (pin "2") (pinfunction "GND_2") (pintype "power_in"))
      (node (ref "IC2") (pin "1") (pinfunction "GND_1") (pintype "power_in"))
      (node (ref "JP11") (pin "6") (pinfunction "6_6") (pintype "passive"))
      (node (ref "JP11") (pin "7") (pinfunction "7_7") (pintype "passive"))
      (node (ref "JP4") (pin "7") (pinfunction "7_7") (pintype "passive"))
      (node (ref "JP8") (pin "24") (pinfunction "24_24") (pintype "passive"))
      (node (ref "JP8") (pin "25") (pinfunction "25_25") (pintype "passive"))
      (node (ref "JP8") (pin "35") (pinfunction "35_35") (pintype "passive"))
      (node (ref "JP8") (pin "36") (pinfunction "36_36") (pintype "passive"))
      (node (ref "LED10") (pin "C") (pinfunction "C_C") (pintype "passive"))
      (node (ref "MDL1") (pin "9") (pinfunction "GND_9") (pintype "bidirectional"))
      (node (ref "PWR") (pin "C") (pinfunction "C_C") (pintype "passive"))
      (node (ref "Q4") (pin "1") (pinfunction "G_1") (pintype "passive"))
      (node (ref "R4") (pin "2") (pinfunction "2_2") (pintype "passive"))
      (node (ref "RESET") (pin "2") (pinfunction "2_2") (pintype "passive"))
      (node (ref "RN4") (pin "3") (pinfunction "2_3") (pintype "passive"))
      (node (ref "SJ1") (pin "1") (pinfunction "1_1") (pintype "passive"))
      (node (ref "SJ2") (pin "1") (pinfunction "1_1") (pintype "passive"))
      (node (ref "SJ3") (pin "1") (pinfunction "1_1") (pintype "passive"))
      (node (ref "SPI") (pin "6") (pinfunction "6_6") (pintype "passive"))
      (node (ref "TEENSY_3.1/3.2") (pin "AGND") (pinfunction "AGND_AGND") (pintype "power_in"))
      (node (ref "TEENSY_3.1/3.2") (pin "GND") (pinfunction "GND_GND") (pintype "power_in"))
      (node (ref "TEENSY_3.1/3.2") (pin "GND1") (pinfunction "GND_GND1") (pintype "power_in"))
      (node (ref "TEENSY_3.1/3.2") (pin "GND2") (pinfunction "GND_GND2") (pintype "power_in"))
      (node (ref "X1") (pin "3") (pinfunction "3_3") (pintype "power_in"))
    )
    (net (code "101") (name "Net-(D1-A)") (class "Default")
      (node (ref "D1") (pin "P$2") (pinfunction "A_P$2") (pintype "bidirectional"))
      (node (ref "L1") (pin "1") (pinfunction "1_1") (pintype "passive"))
    )
    (net (code "102") (name "Net-(D13-PadA)") (class "Default")
      (node (ref "D13") (pin "A") (pinfunction "A_A") (pintype "passive"))
      (node (ref "RN1") (pin "1") (pinfunction "1_1") (pintype "passive"))
    )
    (net (code "103") (name "Net-(RN1D-2)") (class "Default")
      (node (ref "PWR") (pin "A") (pinfunction "A_A") (pintype "passive"))
      (node (ref "RN1") (pin "5") (pinfunction "2_5") (pintype "passive"))
    )
    (net (code "104") (name "Net-(RN6B-1)") (class "Default")
      (node (ref "RN6") (pin "1") (pinfunction "1_1") (pintype "passive"))
      (node (ref "RN6") (pin "2") (pinfunction "1_2") (pintype "passive"))
      (node (ref "RN6") (pin "3") (pinfunction "1_3") (pintype "passive"))
      (node (ref "RN6") (pin "4") (pinfunction "1_4") (pintype "passive"))
      (node (ref "SJ5") (pin "1") (pinfunction "1_1") (pintype "passive"))
    )
    (net (code "105") (name "unconnected-(ESP-PGM-Pad1)") (class "Default")
      (node (ref "ESP-PGM") (pin "1") (pinfunction "1_1") (pintype "passive"))
    )
    (net (code "106") (name "unconnected-(ESP-PGM-Pad3)") (class "Default")
      (node (ref "ESP-PGM") (pin "3") (pinfunction "3_3") (pintype "passive"))
    )
    (net (code "107") (name "unconnected-(ESP-RST-Pad1)") (class "Default")
      (node (ref "ESP-RST") (pin "1") (pinfunction "1_1") (pintype "passive"))
    )
    (net (code "108") (name "unconnected-(ESP-RST-Pad3)") (class "Default")
      (node (ref "ESP-RST") (pin "3") (pinfunction "3_3") (pintype "passive"))
    )
    (net (code "109") (name "unconnected-(HC-PGM-Pad1)") (class "Default")
      (node (ref "HC-PGM") (pin "1") (pinfunction "1_1") (pintype "passive"))
    )
    (net (code "110") (name "unconnected-(HC-PGM-Pad3)") (class "Default")
      (node (ref "HC-PGM") (pin "3") (pinfunction "3_3") (pintype "passive"))
    )
    (net (code "111") (name "unconnected-(JP8-Pad33)") (class "Default")
      (node (ref "JP8") (pin "33") (pinfunction "33_33") (pintype "passive"))
    )
    (net (code "112") (name "unconnected-(JP8-Pad34)") (class "Default")
      (node (ref "JP8") (pin "34") (pinfunction "34_34") (pintype "passive"))
    )
    (net (code "113") (name "unconnected-(JP11-Pad1)") (class "Default")
      (node (ref "JP11") (pin "1") (pinfunction "1_1") (pintype "passive"))
    )
    (net (code "114") (name "unconnected-(RESET-Pad1)") (class "Default")
      (node (ref "RESET") (pin "1") (pinfunction "1_1") (pintype "passive"))
    )
    (net (code "115") (name "unconnected-(RESET-Pad4)") (class "Default")
      (node (ref "RESET") (pin "4") (pinfunction "4_4") (pintype "passive"))
    )
  )
)
